# SparkFun_MOSFET_Power_Controller.net
KiCad netlist of a schematic drawn in EAGLE
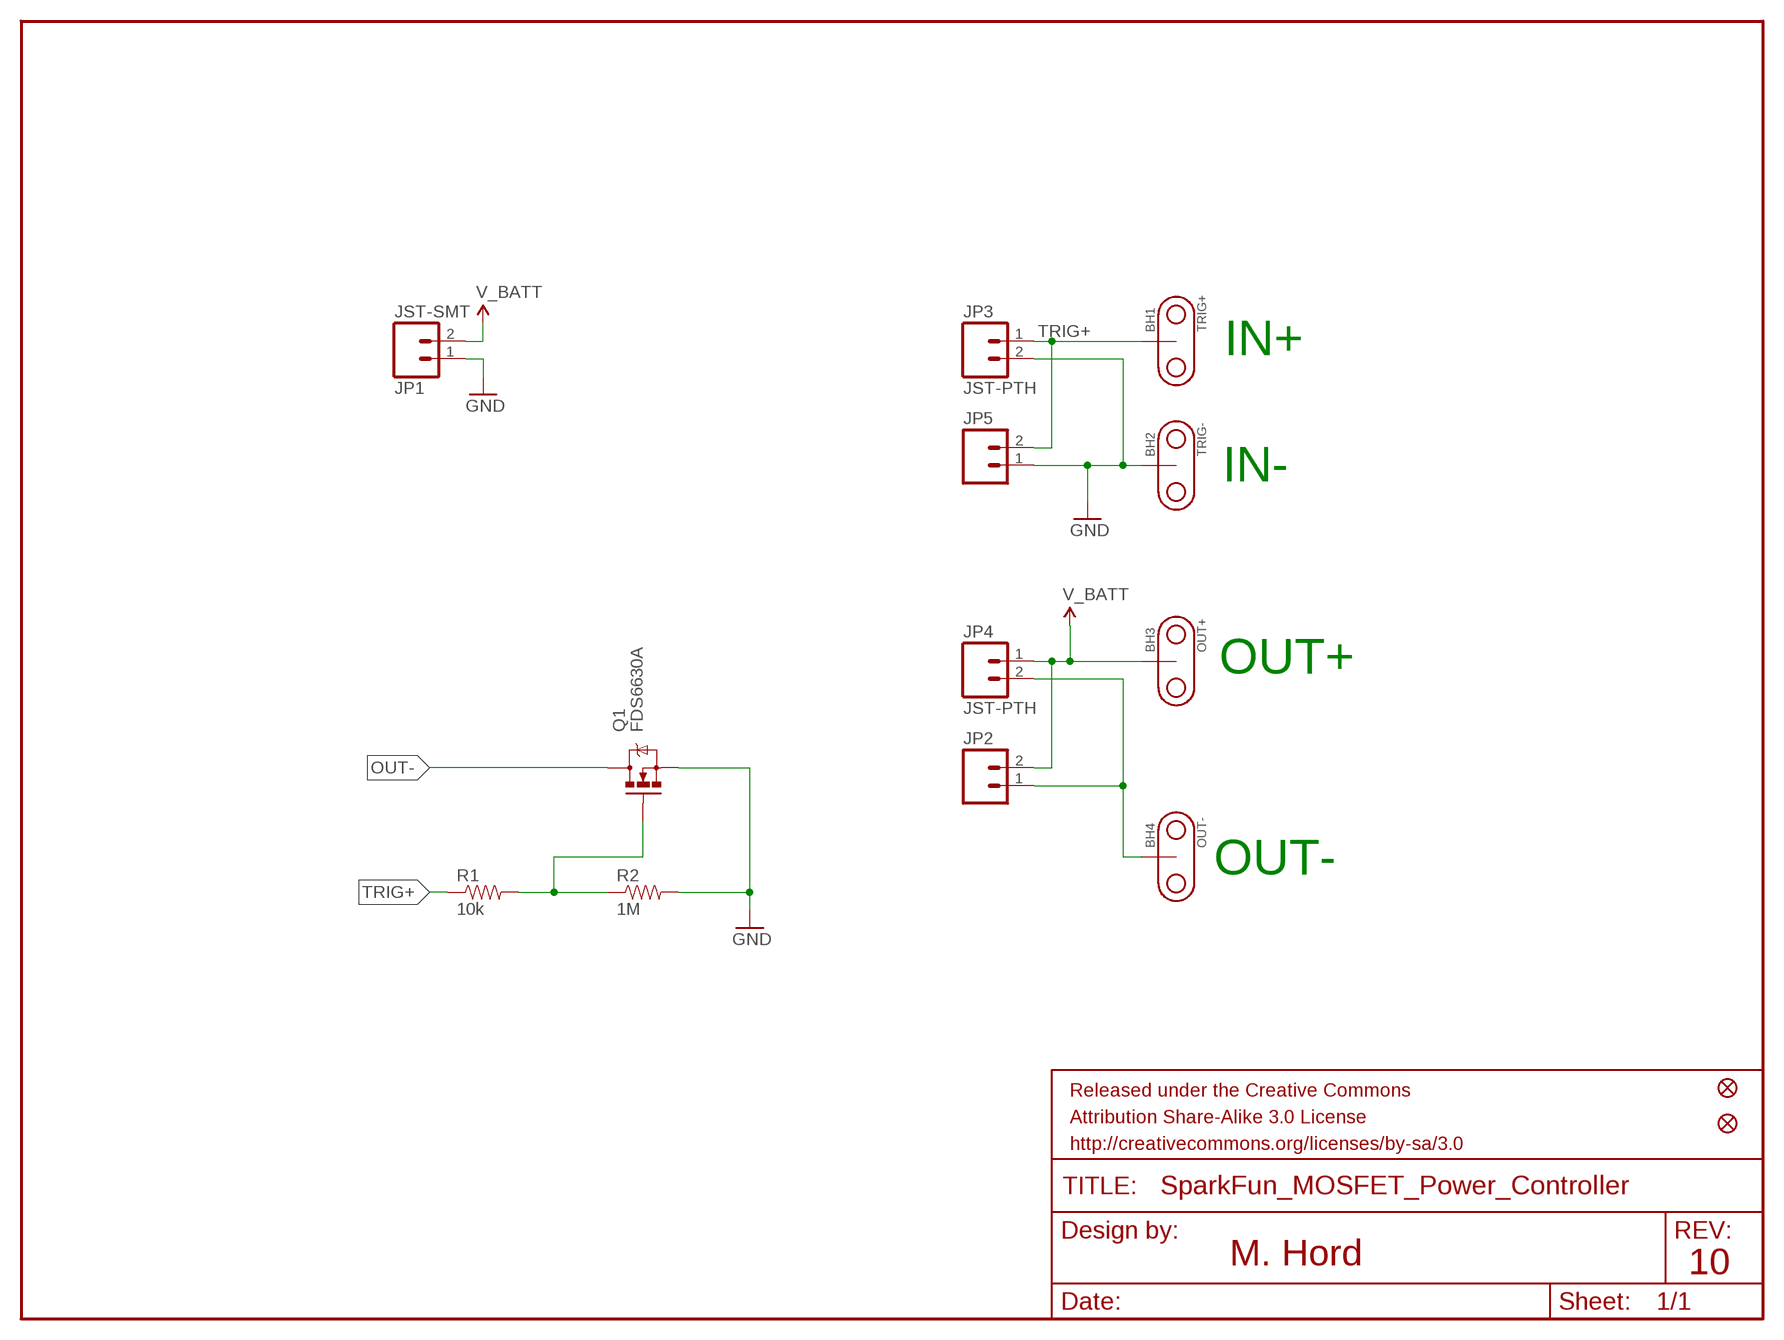
[diagram p0: schematic, sheet 1]

(export (version "E")
  (design (tool "Eeschema 10.0.6"))
  (components
    (comp (ref "BH1")
      (value "TRIG+")
      (footprint "eagle-import:BUTTONHOLE")
      (fields (field (name "NO_PART") "1"))
      (libsource (lib "eagle-import") (part "BUTTONHOLELARGE"))
    )
    (comp (ref "BH2")
      (value "TRIG-")
      (footprint "eagle-import:BUTTONHOLE")
      (fields (field (name "NO_PART") "1"))
      (libsource (lib "eagle-import") (part "BUTTONHOLELARGE"))
    )
    (comp (ref "BH3")
      (value "OUT+")
      (footprint "eagle-import:BUTTONHOLE")
      (fields (field (name "NO_PART") "1"))
      (libsource (lib "eagle-import") (part "BUTTONHOLELARGE"))
    )
    (comp (ref "BH4")
      (value "OUT-")
      (footprint "eagle-import:BUTTONHOLE")
      (fields (field (name "NO_PART") "1"))
      (libsource (lib "eagle-import") (part "BUTTONHOLELARGE"))
    )
    (comp (ref "FRAME1")
      (value "FRAME-LETTER")
      (footprint "eagle-import:CREATIVE_COMMONS")
      (libsource (lib "eagle-import") (part "FRAME-LETTER"))
    )
    (comp (ref "JP1")
      (value "JST-SMT")
      (footprint "eagle-import:JST-2-SMD")
      (fields (field (name "PROD_ID") "CONN-08352"))
      (libsource (lib "eagle-import") (part "M02-JST-2MM-SMT"))
    )
    (comp (ref "JP2")
      (value "M02PTH")
      (footprint "eagle-import:1X02")
      (libsource (lib "eagle-import") (part "M02PTH"))
    )
    (comp (ref "JP3")
      (value "JST-PTH")
      (footprint "eagle-import:JST-2-PTH-NS")
      (fields (field (name "NO_PART") "1"))
      (libsource (lib "eagle-import") (part "M02-JST-2-PTH-NO_SILK"))
    )
    (comp (ref "JP4")
      (value "JST-PTH")
      (footprint "eagle-import:JST-2-PTH-NS")
      (fields (field (name "NO_PART") "1"))
      (libsource (lib "eagle-import") (part "M02-JST-2-PTH-NO_SILK"))
    )
    (comp (ref "JP5")
      (value "M02PTH")
      (footprint "eagle-import:1X02")
      (libsource (lib "eagle-import") (part "M02PTH"))
    )
    (comp (ref "JP6")
      (value "FIDUCIALUFIDUCIAL")
      (footprint "eagle-import:MICRO-FIDUCIAL")
      (libsource (lib "eagle-import") (part "FIDUCIALUFIDUCIAL"))
    )
    (comp (ref "JP7")
      (value "FIDUCIALUFIDUCIAL")
      (footprint "eagle-import:MICRO-FIDUCIAL")
      (libsource (lib "eagle-import") (part "FIDUCIALUFIDUCIAL"))
    )
    (comp (ref "Q1")
      (value "FDS6630A")
      (footprint "eagle-import:SO08")
      (libsource (lib "eagle-import") (part "MOSFET-NCHANNELFDS6630A"))
    )
    (comp (ref "R1")
      (value "10k")
      (footprint "eagle-import:0402-RES")
      (libsource (lib "eagle-import") (part "RESISTOR0402-RES"))
    )
    (comp (ref "R2")
      (value "1M")
      (footprint "eagle-import:0402-RES")
      (libsource (lib "eagle-import") (part "1M-1%"))
    )
  )
  (nets
    (net (code "1") (name "GND") (class "Default")
      (node (ref "BH2") (pin "P$1") (pinfunction "P$1_P$1") (pintype "bidirectional"))
      (node (ref "JP1") (pin "1") (pinfunction "2_1") (pintype "passive"))
      (node (ref "JP3") (pin "2") (pinfunction "2_2") (pintype "passive"))
      (node (ref "JP5") (pin "1") (pinfunction "1_1") (pintype "passive"))
      (node (ref "Q1") (pin "1") (pinfunction "S_1") (pintype "passive"))
      (node (ref "Q1") (pin "2") (pinfunction "S_2") (pintype "passive"))
      (node (ref "Q1") (pin "3") (pinfunction "S_3") (pintype "passive"))
      (node (ref "R2") (pin "2") (pinfunction "2_2") (pintype "passive"))
    )
    (net (code "2") (name "Net-(Q1-G)") (class "Default")
      (node (ref "Q1") (pin "4") (pinfunction "G_4") (pintype "passive"))
      (node (ref "R1") (pin "2") (pinfunction "2_2") (pintype "passive"))
      (node (ref "R2") (pin "1") (pinfunction "1_1") (pintype "passive"))
    )
    (net (code "3") (name "OUT-") (class "Default")
      (node (ref "BH4") (pin "P$1") (pinfunction "P$1_P$1") (pintype "bidirectional"))
      (node (ref "JP2") (pin "1") (pinfunction "1_1") (pintype "passive"))
      (node (ref "JP4") (pin "2") (pinfunction "2_2") (pintype "passive"))
      (node (ref "Q1") (pin "5") (pinfunction "D_5") (pintype "passive"))
      (node (ref "Q1") (pin "6") (pinfunction "D_6") (pintype "passive"))
      (node (ref "Q1") (pin "7") (pinfunction "D_7") (pintype "passive"))
      (node (ref "Q1") (pin "8") (pinfunction "D_8") (pintype "passive"))
    )
    (net (code "4") (name "TRIG+") (class "Default")
      (node (ref "BH1") (pin "P$1") (pinfunction "P$1_P$1") (pintype "bidirectional"))
      (node (ref "JP3") (pin "1") (pinfunction "1_1") (pintype "passive"))
      (node (ref "JP5") (pin "2") (pinfunction "2_2") (pintype "passive"))
      (node (ref "R1") (pin "1") (pinfunction "1_1") (pintype "passive"))
    )
    (net (code "5") (name "V_BATT") (class "Default")
      (node (ref "BH3") (pin "P$1") (pinfunction "P$1_P$1") (pintype "bidirectional"))
      (node (ref "JP1") (pin "2") (pinfunction "1_2") (pintype "passive"))
      (node (ref "JP2") (pin "2") (pinfunction "2_2") (pintype "passive"))
      (node (ref "JP4") (pin "1") (pinfunction "1_1") (pintype "passive"))
    )
  )
)
